# weihnachten.net
KiCad netlist of a schematic drawn in Altium Designer
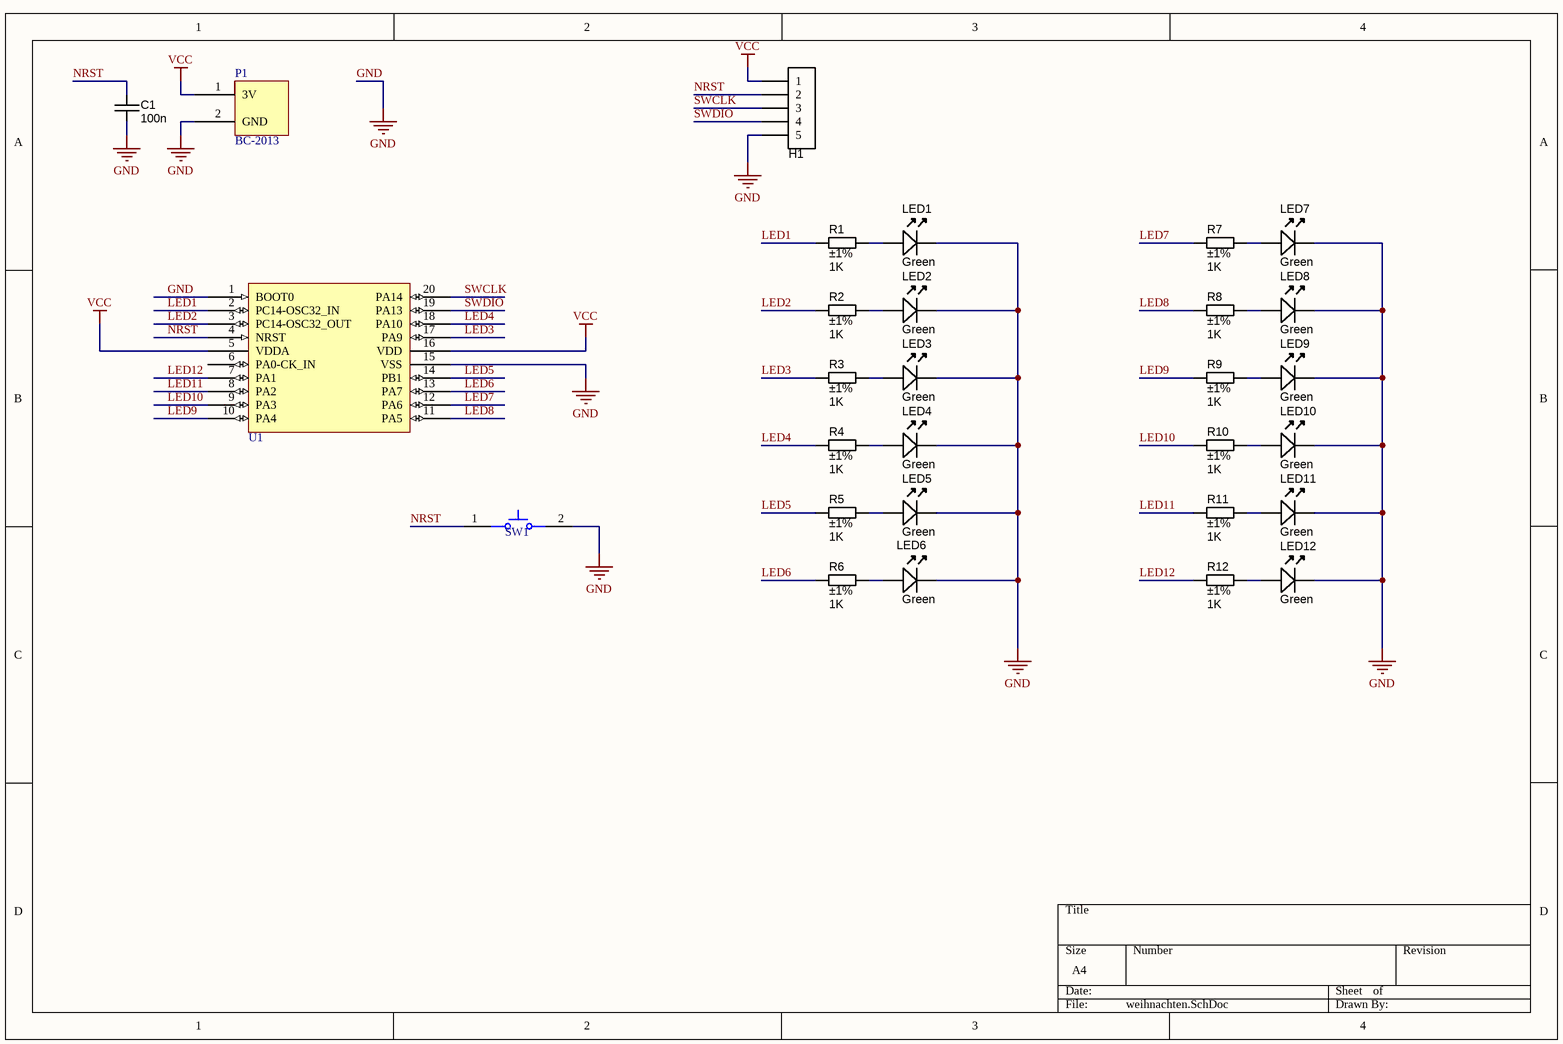
[diagram p0: weihnachten.SchDoc]

(export (version "E")
  (design (tool "Eeschema 10.0.6"))
  (components
    (comp (ref "C1")
      (value "100n")
      (footprint "CAPC1608X90N")
      (description "Capacitor SMD Cer 2.2uF 10% 10V X5R 0603")
      (fields (field (name "TOLERANCE") "±10%") (field (name "Comment") "CAPC_2u2_0603_10V_10%"))
      (libsource (lib "PBL - Capacitors") (part "CAPC_2u2_0603_10V_10%"))
    )
    (comp (ref "H1")
      (value "Programmer")
      (footprint "HDR1X5_2.54MMP")
      (description "Header 5-pin")
      (libsource (lib "PBL - Connectors") (part "Header5P"))
    )
    (comp (ref "LED1")
      (value "Green")
      (footprint "LED-0603-GREEN")
      (description "LED 0603 SMD Green 570nm 50mcd 20mA")
      (libsource (lib "PBL - Light Sources") (part "LED_SMD_Green_0603_570nm"))
    )
    (comp (ref "LED2")
      (value "Green")
      (footprint "LED-0603-GREEN")
      (description "LED 0603 SMD Green 570nm 50mcd 20mA")
      (libsource (lib "PBL - Light Sources") (part "LED_SMD_Green_0603_570nm"))
    )
    (comp (ref "LED3")
      (value "Green")
      (footprint "LED-0603-GREEN")
      (description "LED 0603 SMD Green 570nm 50mcd 20mA")
      (libsource (lib "PBL - Light Sources") (part "LED_SMD_Green_0603_570nm"))
    )
    (comp (ref "LED4")
      (value "Green")
      (footprint "LED-0603-GREEN")
      (description "LED 0603 SMD Green 570nm 50mcd 20mA")
      (libsource (lib "PBL - Light Sources") (part "LED_SMD_Green_0603_570nm"))
    )
    (comp (ref "LED5")
      (value "Green")
      (footprint "LED-0603-GREEN")
      (description "LED 0603 SMD Green 570nm 50mcd 20mA")
      (libsource (lib "PBL - Light Sources") (part "LED_SMD_Green_0603_570nm"))
    )
    (comp (ref "LED6")
      (value "Green")
      (footprint "LED-0603-GREEN")
      (description "LED 0603 SMD Green 570nm 50mcd 20mA")
      (libsource (lib "PBL - Light Sources") (part "LED_SMD_Green_0603_570nm"))
    )
    (comp (ref "LED7")
      (value "Green")
      (footprint "LED-0603-GREEN")
      (description "LED 0603 SMD Green 570nm 50mcd 20mA")
      (libsource (lib "PBL - Light Sources") (part "LED_SMD_Green_0603_570nm"))
    )
    (comp (ref "LED8")
      (value "Green")
      (footprint "LED-0603-GREEN")
      (description "LED 0603 SMD Green 570nm 50mcd 20mA")
      (libsource (lib "PBL - Light Sources") (part "LED_SMD_Green_0603_570nm"))
    )
    (comp (ref "LED9")
      (value "Green")
      (footprint "LED-0603-GREEN")
      (description "LED 0603 SMD Green 570nm 50mcd 20mA")
      (libsource (lib "PBL - Light Sources") (part "LED_SMD_Green_0603_570nm"))
    )
    (comp (ref "LED10")
      (value "Green")
      (footprint "LED-0603-GREEN")
      (description "LED 0603 SMD Green 570nm 50mcd 20mA")
      (libsource (lib "PBL - Light Sources") (part "LED_SMD_Green_0603_570nm"))
    )
    (comp (ref "LED11")
      (value "Green")
      (footprint "LED-0603-GREEN")
      (description "LED 0603 SMD Green 570nm 50mcd 20mA")
      (libsource (lib "PBL - Light Sources") (part "LED_SMD_Green_0603_570nm"))
    )
    (comp (ref "LED12")
      (value "Green")
      (footprint "LED-0603-GREEN")
      (description "LED 0603 SMD Green 570nm 50mcd 20mA")
      (libsource (lib "PBL - Light Sources") (part "LED_SMD_Green_0603_570nm"))
    )
    (comp (ref "P1") (value "BC-2013") (footprint "BC-2013-ND") (libsource (lib "lib") (part "BC-2013")))
    (comp (ref "R1")
      (value "1K")
      (footprint "RESC1608X55N")
      (description "Resistor SMD chip 1k Ohm 0.1W 1% 0603")
      (fields (field (name "TOLERANCE") "±1%") (field (name "Comment") "Thick Film"))
      (libsource (lib "PBL - Resistors") (part "RES_1K_0603_1%"))
    )
    (comp (ref "R2")
      (value "1K")
      (footprint "RESC1608X55N")
      (description "Resistor SMD chip 1k Ohm 0.1W 1% 0603")
      (fields (field (name "TOLERANCE") "±1%") (field (name "Comment") "Thick Film"))
      (libsource (lib "PBL - Resistors") (part "RES_1K_0603_1%"))
    )
    (comp (ref "R3")
      (value "1K")
      (footprint "RESC1608X55N")
      (description "Resistor SMD chip 1k Ohm 0.1W 1% 0603")
      (fields (field (name "TOLERANCE") "±1%") (field (name "Comment") "Thick Film"))
      (libsource (lib "PBL - Resistors") (part "RES_1K_0603_1%"))
    )
    (comp (ref "R4")
      (value "1K")
      (footprint "RESC1608X55N")
      (description "Resistor SMD chip 1k Ohm 0.1W 1% 0603")
      (fields (field (name "TOLERANCE") "±1%") (field (name "Comment") "Thick Film"))
      (libsource (lib "PBL - Resistors") (part "RES_1K_0603_1%"))
    )
    (comp (ref "R5")
      (value "1K")
      (footprint "RESC1608X55N")
      (description "Resistor SMD chip 1k Ohm 0.1W 1% 0603")
      (fields (field (name "TOLERANCE") "±1%") (field (name "Comment") "Thick Film"))
      (libsource (lib "PBL - Resistors") (part "RES_1K_0603_1%"))
    )
    (comp (ref "R6")
      (value "1K")
      (footprint "RESC1608X55N")
      (description "Resistor SMD chip 1k Ohm 0.1W 1% 0603")
      (fields (field (name "TOLERANCE") "±1%") (field (name "Comment") "Thick Film"))
      (libsource (lib "PBL - Resistors") (part "RES_1K_0603_1%"))
    )
    (comp (ref "R7")
      (value "1K")
      (footprint "RESC1608X55N")
      (description "Resistor SMD chip 1k Ohm 0.1W 1% 0603")
      (fields (field (name "TOLERANCE") "±1%") (field (name "Comment") "Thick Film"))
      (libsource (lib "PBL - Resistors") (part "RES_1K_0603_1%"))
    )
    (comp (ref "R8")
      (value "1K")
      (footprint "RESC1608X55N")
      (description "Resistor SMD chip 1k Ohm 0.1W 1% 0603")
      (fields (field (name "TOLERANCE") "±1%") (field (name "Comment") "Thick Film"))
      (libsource (lib "PBL - Resistors") (part "RES_1K_0603_1%"))
    )
    (comp (ref "R9")
      (value "1K")
      (footprint "RESC1608X55N")
      (description "Resistor SMD chip 1k Ohm 0.1W 1% 0603")
      (fields (field (name "TOLERANCE") "±1%") (field (name "Comment") "Thick Film"))
      (libsource (lib "PBL - Resistors") (part "RES_1K_0603_1%"))
    )
    (comp (ref "R10")
      (value "1K")
      (footprint "RESC1608X55N")
      (description "Resistor SMD chip 1k Ohm 0.1W 1% 0603")
      (fields (field (name "TOLERANCE") "±1%") (field (name "Comment") "Thick Film"))
      (libsource (lib "PBL - Resistors") (part "RES_1K_0603_1%"))
    )
    (comp (ref "R11")
      (value "1K")
      (footprint "RESC1608X55N")
      (description "Resistor SMD chip 1k Ohm 0.1W 1% 0603")
      (fields (field (name "TOLERANCE") "±1%") (field (name "Comment") "Thick Film"))
      (libsource (lib "PBL - Resistors") (part "RES_1K_0603_1%"))
    )
    (comp (ref "R12")
      (value "1K")
      (footprint "RESC1608X55N")
      (description "Resistor SMD chip 1k Ohm 0.1W 1% 0603")
      (fields (field (name "TOLERANCE") "±1%") (field (name "Comment") "Thick Film"))
      (libsource (lib "PBL - Resistors") (part "RES_1K_0603_1%"))
    )
    (comp (ref "SW1")
      (value "B3U-1000P")
      (footprint "OMRON-B3U-1000_V")
      (description "Ultra-Small Tactile Switch, 0.05 A, 12 V, -25 to 70 degC, 2-Pin SMD, RoHS, Tape and Reel")
      (fields (field (name "MANUFACTURER") "Omron Electronic Components"))
      (libsource (lib "Altium Content Vault") (part "CMP-2100-03586-1"))
    )
    (comp (ref "U1")
      (value "STM32L031F6")
      (footprint "STM32L031F6")
      (libsource (lib "lib") (part "STM32L031F6"))
    )
  )
  (nets
    (net (code "1") (name "/LED1") (class "Default")
      (node (ref "R1") (pin "1") (pinfunction "1_1") (pintype "passive"))
      (node (ref "U1") (pin "2") (pinfunction "PC14-OSC32_IN_2") (pintype "bidirectional"))
    )
    (net (code "2") (name "/LED2") (class "Default")
      (node (ref "R2") (pin "1") (pinfunction "1_1") (pintype "passive"))
      (node (ref "U1") (pin "3") (pinfunction "PC14-OSC32_OUT_3") (pintype "bidirectional"))
    )
    (net (code "3") (name "/LED3") (class "Default")
      (node (ref "R3") (pin "1") (pinfunction "1_1") (pintype "passive"))
      (node (ref "U1") (pin "17") (pinfunction "PA9_17") (pintype "bidirectional"))
    )
    (net (code "4") (name "/LED4") (class "Default")
      (node (ref "R4") (pin "1") (pinfunction "1_1") (pintype "passive"))
      (node (ref "U1") (pin "18") (pinfunction "PA10_18") (pintype "bidirectional"))
    )
    (net (code "5") (name "/LED5") (class "Default")
      (node (ref "R5") (pin "1") (pinfunction "1_1") (pintype "passive"))
      (node (ref "U1") (pin "14") (pinfunction "PB1_14") (pintype "bidirectional"))
    )
    (net (code "6") (name "/LED6") (class "Default")
      (node (ref "R6") (pin "1") (pinfunction "1_1") (pintype "passive"))
      (node (ref "U1") (pin "13") (pinfunction "PA7_13") (pintype "bidirectional"))
    )
    (net (code "7") (name "/LED7") (class "Default")
      (node (ref "R7") (pin "1") (pinfunction "1_1") (pintype "passive"))
      (node (ref "U1") (pin "12") (pinfunction "PA6_12") (pintype "bidirectional"))
    )
    (net (code "8") (name "/LED8") (class "Default")
      (node (ref "R8") (pin "1") (pinfunction "1_1") (pintype "passive"))
      (node (ref "U1") (pin "11") (pinfunction "PA5_11") (pintype "bidirectional"))
    )
    (net (code "9") (name "/LED9") (class "Default")
      (node (ref "R9") (pin "1") (pinfunction "1_1") (pintype "passive"))
      (node (ref "U1") (pin "10") (pinfunction "PA4_10") (pintype "bidirectional"))
    )
    (net (code "10") (name "/LED10") (class "Default")
      (node (ref "R10") (pin "1") (pinfunction "1_1") (pintype "passive"))
      (node (ref "U1") (pin "9") (pinfunction "PA3_9") (pintype "bidirectional"))
    )
    (net (code "11") (name "/LED11") (class "Default")
      (node (ref "R11") (pin "1") (pinfunction "1_1") (pintype "passive"))
      (node (ref "U1") (pin "8") (pinfunction "PA2_8") (pintype "bidirectional"))
    )
    (net (code "12") (name "/LED12") (class "Default")
      (node (ref "R12") (pin "1") (pinfunction "1_1") (pintype "passive"))
      (node (ref "U1") (pin "7") (pinfunction "PA1_7") (pintype "bidirectional"))
    )
    (net (code "13") (name "/NRST") (class "Default")
      (node (ref "C1") (pin "2") (pintype "passive"))
      (node (ref "H1") (pin "2") (pinfunction "2_2") (pintype "passive"))
      (node (ref "SW1") (pin "1") (pinfunction "1_1") (pintype "passive"))
      (node (ref "U1") (pin "4") (pinfunction "NRST_4") (pintype "input"))
    )
    (net (code "14") (name "/SWCLK") (class "Default")
      (node (ref "H1") (pin "3") (pinfunction "3_3") (pintype "passive"))
      (node (ref "U1") (pin "20") (pinfunction "PA14_20") (pintype "bidirectional"))
    )
    (net (code "15") (name "/SWDIO") (class "Default")
      (node (ref "H1") (pin "4") (pinfunction "4_4") (pintype "passive"))
      (node (ref "U1") (pin "19") (pinfunction "PA13_19") (pintype "bidirectional"))
    )
    (net (code "16") (name "GND") (class "Default")
      (node (ref "C1") (pin "1") (pintype "passive"))
      (node (ref "H1") (pin "5") (pinfunction "5_5") (pintype "passive"))
      (node (ref "LED1") (pin "K") (pinfunction "K_K") (pintype "passive"))
      (node (ref "LED10") (pin "K") (pinfunction "K_K") (pintype "passive"))
      (node (ref "LED11") (pin "K") (pinfunction "K_K") (pintype "passive"))
      (node (ref "LED12") (pin "K") (pinfunction "K_K") (pintype "passive"))
      (node (ref "LED2") (pin "K") (pinfunction "K_K") (pintype "passive"))
      (node (ref "LED3") (pin "K") (pinfunction "K_K") (pintype "passive"))
      (node (ref "LED4") (pin "K") (pinfunction "K_K") (pintype "passive"))
      (node (ref "LED5") (pin "K") (pinfunction "K_K") (pintype "passive"))
      (node (ref "LED6") (pin "K") (pinfunction "K_K") (pintype "passive"))
      (node (ref "LED7") (pin "K") (pinfunction "K_K") (pintype "passive"))
      (node (ref "LED8") (pin "K") (pinfunction "K_K") (pintype "passive"))
      (node (ref "LED9") (pin "K") (pinfunction "K_K") (pintype "passive"))
      (node (ref "P1") (pin "2") (pinfunction "GND_2") (pintype "power_in"))
      (node (ref "SW1") (pin "2") (pinfunction "2_2") (pintype "passive"))
      (node (ref "U1") (pin "1") (pinfunction "BOOT0_1") (pintype "input"))
      (node (ref "U1") (pin "15") (pinfunction "VSS_15") (pintype "power_in"))
    )
    (net (code "17") (name "Net-(LED1-PadA)") (class "Default")
      (node (ref "LED1") (pin "A") (pinfunction "A_A") (pintype "passive"))
      (node (ref "R1") (pin "2") (pinfunction "2_2") (pintype "passive"))
    )
    (net (code "18") (name "Net-(LED2-PadA)") (class "Default")
      (node (ref "LED2") (pin "A") (pinfunction "A_A") (pintype "passive"))
      (node (ref "R2") (pin "2") (pinfunction "2_2") (pintype "passive"))
    )
    (net (code "19") (name "Net-(LED3-PadA)") (class "Default")
      (node (ref "LED3") (pin "A") (pinfunction "A_A") (pintype "passive"))
      (node (ref "R3") (pin "2") (pinfunction "2_2") (pintype "passive"))
    )
    (net (code "20") (name "Net-(LED4-PadA)") (class "Default")
      (node (ref "LED4") (pin "A") (pinfunction "A_A") (pintype "passive"))
      (node (ref "R4") (pin "2") (pinfunction "2_2") (pintype "passive"))
    )
    (net (code "21") (name "Net-(LED5-PadA)") (class "Default")
      (node (ref "LED5") (pin "A") (pinfunction "A_A") (pintype "passive"))
      (node (ref "R5") (pin "2") (pinfunction "2_2") (pintype "passive"))
    )
    (net (code "22") (name "Net-(LED6-PadA)") (class "Default")
      (node (ref "LED6") (pin "A") (pinfunction "A_A") (pintype "passive"))
      (node (ref "R6") (pin "2") (pinfunction "2_2") (pintype "passive"))
    )
    (net (code "23") (name "Net-(LED7-PadA)") (class "Default")
      (node (ref "LED7") (pin "A") (pinfunction "A_A") (pintype "passive"))
      (node (ref "R7") (pin "2") (pinfunction "2_2") (pintype "passive"))
    )
    (net (code "24") (name "Net-(LED8-PadA)") (class "Default")
      (node (ref "LED8") (pin "A") (pinfunction "A_A") (pintype "passive"))
      (node (ref "R8") (pin "2") (pinfunction "2_2") (pintype "passive"))
    )
    (net (code "25") (name "Net-(LED9-PadA)") (class "Default")
      (node (ref "LED9") (pin "A") (pinfunction "A_A") (pintype "passive"))
      (node (ref "R9") (pin "2") (pinfunction "2_2") (pintype "passive"))
    )
    (net (code "26") (name "Net-(LED10-PadA)") (class "Default")
      (node (ref "LED10") (pin "A") (pinfunction "A_A") (pintype "passive"))
      (node (ref "R10") (pin "2") (pinfunction "2_2") (pintype "passive"))
    )
    (net (code "27") (name "Net-(LED11-PadA)") (class "Default")
      (node (ref "LED11") (pin "A") (pinfunction "A_A") (pintype "passive"))
      (node (ref "R11") (pin "2") (pinfunction "2_2") (pintype "passive"))
    )
    (net (code "28") (name "Net-(LED12-PadA)") (class "Default")
      (node (ref "LED12") (pin "A") (pinfunction "A_A") (pintype "passive"))
      (node (ref "R12") (pin "2") (pinfunction "2_2") (pintype "passive"))
    )
    (net (code "29") (name "VCC") (class "Default")
      (node (ref "H1") (pin "1") (pinfunction "1_1") (pintype "passive"))
      (node (ref "P1") (pin "1") (pinfunction "3V_1") (pintype "power_in"))
      (node (ref "U1") (pin "16") (pinfunction "VDD_16") (pintype "power_in"))
      (node (ref "U1") (pin "5") (pinfunction "VDDA_5") (pintype "power_in"))
    )
    (net (code "30") (name "unconnected-(U1-PA0-CK_IN-Pad6)") (class "Default")
      (node (ref "U1") (pin "6") (pinfunction "PA0-CK_IN_6") (pintype "bidirectional"))
    )
  )
)
